# Filter_Capacitors_-_External_SIM.net
KiCad netlist of a schematic drawn in Altium Designer
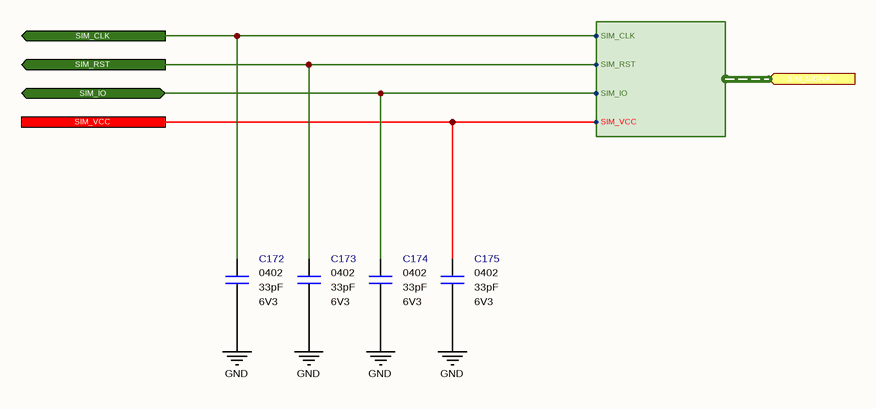
[diagram p0: Filter Capacitors - External SIM.SchDoc]

(export (version "E")
  (design (tool "Eeschema 10.0.6"))
  (components
    (comp (ref "C172")
      (value "33pF")
      (footprint "CAPACITOR_0402")
      (description "Capacitor - 33pF [0402] (Ceramic)")
      (fields
        (field (name "TOLERANCE") "10%")
        (field (name "CASE") "0402")
        (field (name "VOLTAGE") "6V3")
        (field (name "MANUFACTURER PART NUMBER") "C0402C330J9RACAUTO")
      )
      (libsource (lib "Ovoo_Library") (part "Capacitor - 33pF [0402-6V3]"))
    )
    (comp (ref "C173")
      (value "33pF")
      (footprint "CAPACITOR_0402")
      (description "Capacitor - 33pF [0402] (Ceramic)")
      (fields
        (field (name "TOLERANCE") "10%")
        (field (name "CASE") "0402")
        (field (name "VOLTAGE") "6V3")
        (field (name "MANUFACTURER PART NUMBER") "C0402C330J9RACAUTO")
      )
      (libsource (lib "Ovoo_Library") (part "Capacitor - 33pF [0402-6V3]"))
    )
    (comp (ref "C174")
      (value "33pF")
      (footprint "CAPACITOR_0402")
      (description "Capacitor - 33pF [0402] (Ceramic)")
      (fields
        (field (name "TOLERANCE") "10%")
        (field (name "CASE") "0402")
        (field (name "VOLTAGE") "6V3")
        (field (name "MANUFACTURER PART NUMBER") "C0402C330J9RACAUTO")
      )
      (libsource (lib "Ovoo_Library") (part "Capacitor - 33pF [0402-6V3]"))
    )
    (comp (ref "C175")
      (value "33pF")
      (footprint "CAPACITOR_0402")
      (description "Capacitor - 33pF [0402] (Ceramic)")
      (fields
        (field (name "TOLERANCE") "10%")
        (field (name "CASE") "0402")
        (field (name "VOLTAGE") "6V3")
        (field (name "MANUFACTURER PART NUMBER") "C0402C330J9RACAUTO")
      )
      (libsource (lib "Ovoo_Library") (part "Capacitor - 33pF [0402-6V3]"))
    )
  )
  (nets
    (net (code "2") (name "/SIM_CLK") (class "Default")
      (node (ref "C172") (pin "2") (pinfunction "2_2") (pintype "passive"))
    )
    (net (code "3") (name "/SIM_IO") (class "Default")
      (node (ref "C174") (pin "2") (pinfunction "2_2") (pintype "passive"))
    )
    (net (code "4") (name "/SIM_RST") (class "Default")
      (node (ref "C173") (pin "2") (pinfunction "2_2") (pintype "passive"))
    )
    (net (code "5") (name "/SIM_VCC") (class "Default")
      (node (ref "C175") (pin "2") (pinfunction "2_2") (pintype "passive"))
    )
    (net (code "7") (name "GND") (class "Default")
      (node (ref "C172") (pin "1") (pinfunction "1_1") (pintype "passive"))
      (node (ref "C173") (pin "1") (pinfunction "1_1") (pintype "passive"))
      (node (ref "C174") (pin "1") (pinfunction "1_1") (pintype "passive"))
      (node (ref "C175") (pin "1") (pinfunction "1_1") (pintype "passive"))
    )
  )
)
